# PanTiltHeader.net
KiCad netlist of a schematic drawn in EAGLE
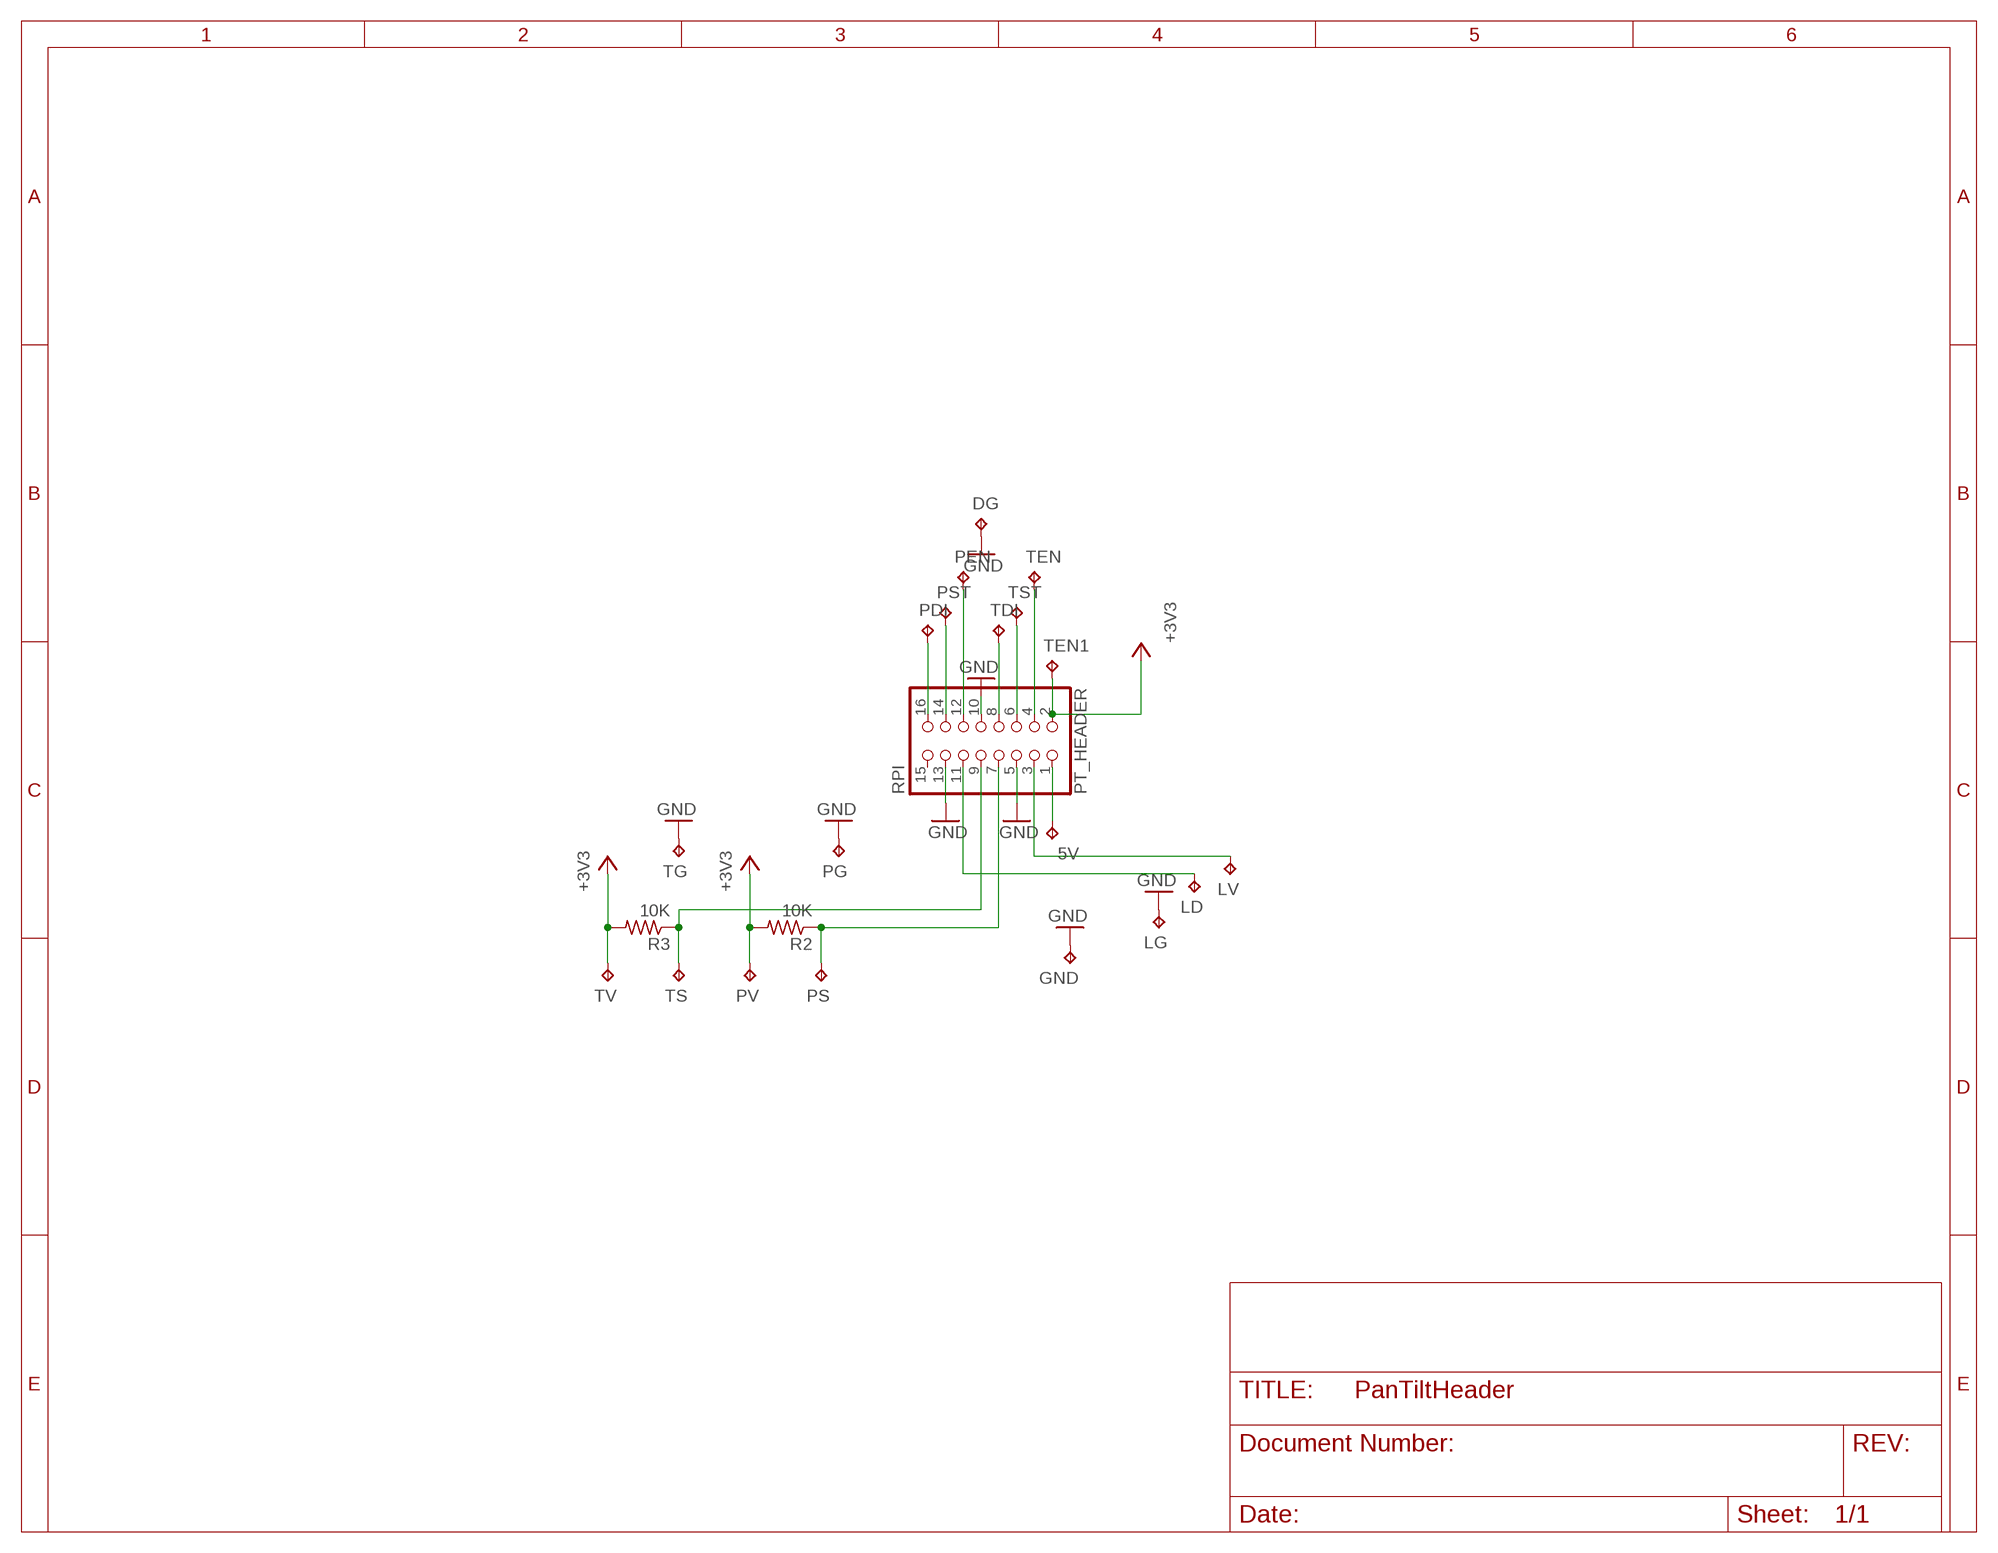
[diagram p0: schematic, sheet 1]

(export (version "E")
  (design (tool "Eeschema 10.0.6"))
  (components
    (comp (ref "5V")
      (value "TPPAD1-13Y")
      (footprint "eagle-import:P1-13Y")
      (libsource (lib "eagle-import") (part "TPPAD1-13Y"))
    )
    (comp (ref "DG")
      (value "TPPAD1-13Y")
      (footprint "eagle-import:P1-13Y")
      (libsource (lib "eagle-import") (part "TPPAD1-13Y"))
    )
    (comp (ref "GND")
      (value "TPPAD1-13Y")
      (footprint "eagle-import:P1-13Y")
      (libsource (lib "eagle-import") (part "TPPAD1-13Y"))
    )
    (comp (ref "LD")
      (value "TPPAD1-13Y")
      (footprint "eagle-import:P1-13Y")
      (libsource (lib "eagle-import") (part "TPPAD1-13Y"))
    )
    (comp (ref "LG")
      (value "TPPAD1-13Y")
      (footprint "eagle-import:P1-13Y")
      (libsource (lib "eagle-import") (part "TPPAD1-13Y"))
    )
    (comp (ref "LV")
      (value "TPPAD1-13Y")
      (footprint "eagle-import:P1-13Y")
      (libsource (lib "eagle-import") (part "TPPAD1-13Y"))
    )
    (comp (ref "PDI")
      (value "TPPAD1-13Y")
      (footprint "eagle-import:P1-13Y")
      (libsource (lib "eagle-import") (part "TPPAD1-13Y"))
    )
    (comp (ref "PEN")
      (value "TPPAD1-13Y")
      (footprint "eagle-import:P1-13Y")
      (libsource (lib "eagle-import") (part "TPPAD1-13Y"))
    )
    (comp (ref "PG")
      (value "TPPAD1-13Y")
      (footprint "eagle-import:P1-13Y")
      (libsource (lib "eagle-import") (part "TPPAD1-13Y"))
    )
    (comp (ref "PS")
      (value "TPPAD1-13Y")
      (footprint "eagle-import:P1-13Y")
      (libsource (lib "eagle-import") (part "TPPAD1-13Y"))
    )
    (comp (ref "PST")
      (value "TPPAD1-13Y")
      (footprint "eagle-import:P1-13Y")
      (libsource (lib "eagle-import") (part "TPPAD1-13Y"))
    )
    (comp (ref "PT_HEADER")
      (value "RPI")
      (footprint "eagle-import:2X08")
      (libsource (lib "eagle-import") (part "PINHD-2X8"))
    )
    (comp (ref "PV")
      (value "TPPAD1-13Y")
      (footprint "eagle-import:P1-13Y")
      (libsource (lib "eagle-import") (part "TPPAD1-13Y"))
    )
    (comp (ref "R2")
      (value "10K")
      (footprint "eagle-import:0204_7")
      (libsource (lib "eagle-import") (part "R-US_0204/7"))
    )
    (comp (ref "R3")
      (value "10K")
      (footprint "eagle-import:0204_7")
      (libsource (lib "eagle-import") (part "R-US_0204/7"))
    )
    (comp (ref "TDI")
      (value "TPPAD1-13Y")
      (footprint "eagle-import:P1-13Y")
      (libsource (lib "eagle-import") (part "TPPAD1-13Y"))
    )
    (comp (ref "TEN")
      (value "TPPAD1-13Y")
      (footprint "eagle-import:P1-13Y")
      (libsource (lib "eagle-import") (part "TPPAD1-13Y"))
    )
    (comp (ref "TEN1")
      (value "TPPAD1-13Y")
      (footprint "eagle-import:P1-13Y")
      (libsource (lib "eagle-import") (part "TPPAD1-13Y"))
    )
    (comp (ref "TG")
      (value "TPPAD1-13Y")
      (footprint "eagle-import:P1-13Y")
      (libsource (lib "eagle-import") (part "TPPAD1-13Y"))
    )
    (comp (ref "TS")
      (value "TPPAD1-13Y")
      (footprint "eagle-import:P1-13Y")
      (libsource (lib "eagle-import") (part "TPPAD1-13Y"))
    )
    (comp (ref "TST")
      (value "TPPAD1-13Y")
      (footprint "eagle-import:P1-13Y")
      (libsource (lib "eagle-import") (part "TPPAD1-13Y"))
    )
    (comp (ref "TV")
      (value "TPPAD1-13Y")
      (footprint "eagle-import:P1-13Y")
      (libsource (lib "eagle-import") (part "TPPAD1-13Y"))
    )
  )
  (nets
    (net (code "1") (name "+3V3") (class "Default")
      (node (ref "PT_HEADER") (pin "2") (pinfunction "2_2") (pintype "passive"))
      (node (ref "PV") (pin "TP") (pinfunction "TP_TP") (pintype "input"))
      (node (ref "R2") (pin "2") (pinfunction "2_2") (pintype "passive"))
      (node (ref "R3") (pin "2") (pinfunction "2_2") (pintype "passive"))
      (node (ref "TEN1") (pin "TP") (pinfunction "TP_TP") (pintype "input"))
      (node (ref "TV") (pin "TP") (pinfunction "TP_TP") (pintype "input"))
    )
    (net (code "2") (name "GND") (class "Default")
      (node (ref "DG") (pin "TP") (pinfunction "TP_TP") (pintype "input"))
      (node (ref "GND") (pin "TP") (pinfunction "TP_TP") (pintype "input"))
      (node (ref "LG") (pin "TP") (pinfunction "TP_TP") (pintype "input"))
      (node (ref "PG") (pin "TP") (pinfunction "TP_TP") (pintype "input"))
      (node (ref "PT_HEADER") (pin "10") (pinfunction "10_10") (pintype "passive"))
      (node (ref "PT_HEADER") (pin "13") (pinfunction "13_13") (pintype "passive"))
      (node (ref "PT_HEADER") (pin "5") (pinfunction "5_5") (pintype "passive"))
      (node (ref "TG") (pin "TP") (pinfunction "TP_TP") (pintype "input"))
    )
    (net (code "3") (name "Net-(5V-PadTP)") (class "Default")
      (node (ref "5V") (pin "TP") (pinfunction "TP_TP") (pintype "input"))
      (node (ref "PT_HEADER") (pin "1") (pinfunction "1_1") (pintype "passive"))
    )
    (net (code "4") (name "Net-(LD-PadTP)") (class "Default")
      (node (ref "LD") (pin "TP") (pinfunction "TP_TP") (pintype "input"))
      (node (ref "PT_HEADER") (pin "11") (pinfunction "11_11") (pintype "passive"))
    )
    (net (code "5") (name "Net-(LV-PadTP)") (class "Default")
      (node (ref "LV") (pin "TP") (pinfunction "TP_TP") (pintype "input"))
      (node (ref "PT_HEADER") (pin "3") (pinfunction "3_3") (pintype "passive"))
    )
    (net (code "6") (name "Net-(PDI-PadTP)") (class "Default")
      (node (ref "PDI") (pin "TP") (pinfunction "TP_TP") (pintype "input"))
      (node (ref "PT_HEADER") (pin "16") (pinfunction "16_16") (pintype "passive"))
    )
    (net (code "7") (name "Net-(PEN-PadTP)") (class "Default")
      (node (ref "PEN") (pin "TP") (pinfunction "TP_TP") (pintype "input"))
      (node (ref "PT_HEADER") (pin "12") (pinfunction "12_12") (pintype "passive"))
    )
    (net (code "8") (name "Net-(PS-PadTP)") (class "Default")
      (node (ref "PS") (pin "TP") (pinfunction "TP_TP") (pintype "input"))
      (node (ref "PT_HEADER") (pin "7") (pinfunction "7_7") (pintype "passive"))
      (node (ref "R2") (pin "1") (pinfunction "1_1") (pintype "passive"))
    )
    (net (code "9") (name "Net-(PST-PadTP)") (class "Default")
      (node (ref "PST") (pin "TP") (pinfunction "TP_TP") (pintype "input"))
      (node (ref "PT_HEADER") (pin "14") (pinfunction "14_14") (pintype "passive"))
    )
    (net (code "10") (name "Net-(PT_HEADER-Pad4)") (class "Default")
      (node (ref "PT_HEADER") (pin "4") (pinfunction "4_4") (pintype "passive"))
      (node (ref "TEN") (pin "TP") (pinfunction "TP_TP") (pintype "input"))
    )
    (net (code "11") (name "Net-(PT_HEADER-Pad6)") (class "Default")
      (node (ref "PT_HEADER") (pin "6") (pinfunction "6_6") (pintype "passive"))
      (node (ref "TST") (pin "TP") (pinfunction "TP_TP") (pintype "input"))
    )
    (net (code "12") (name "Net-(PT_HEADER-Pad8)") (class "Default")
      (node (ref "PT_HEADER") (pin "8") (pinfunction "8_8") (pintype "passive"))
      (node (ref "TDI") (pin "TP") (pinfunction "TP_TP") (pintype "input"))
    )
    (net (code "13") (name "Net-(PT_HEADER-Pad9)") (class "Default")
      (node (ref "PT_HEADER") (pin "9") (pinfunction "9_9") (pintype "passive"))
      (node (ref "R3") (pin "1") (pinfunction "1_1") (pintype "passive"))
      (node (ref "TS") (pin "TP") (pinfunction "TP_TP") (pintype "input"))
    )
    (net (code "14") (name "unconnected-(PT_HEADER-Pad15)") (class "Default")
      (node (ref "PT_HEADER") (pin "15") (pinfunction "15_15") (pintype "passive"))
    )
  )
)
